# schematic_Nokia5110.net
KiCad netlist of a schematic drawn in EAGLE
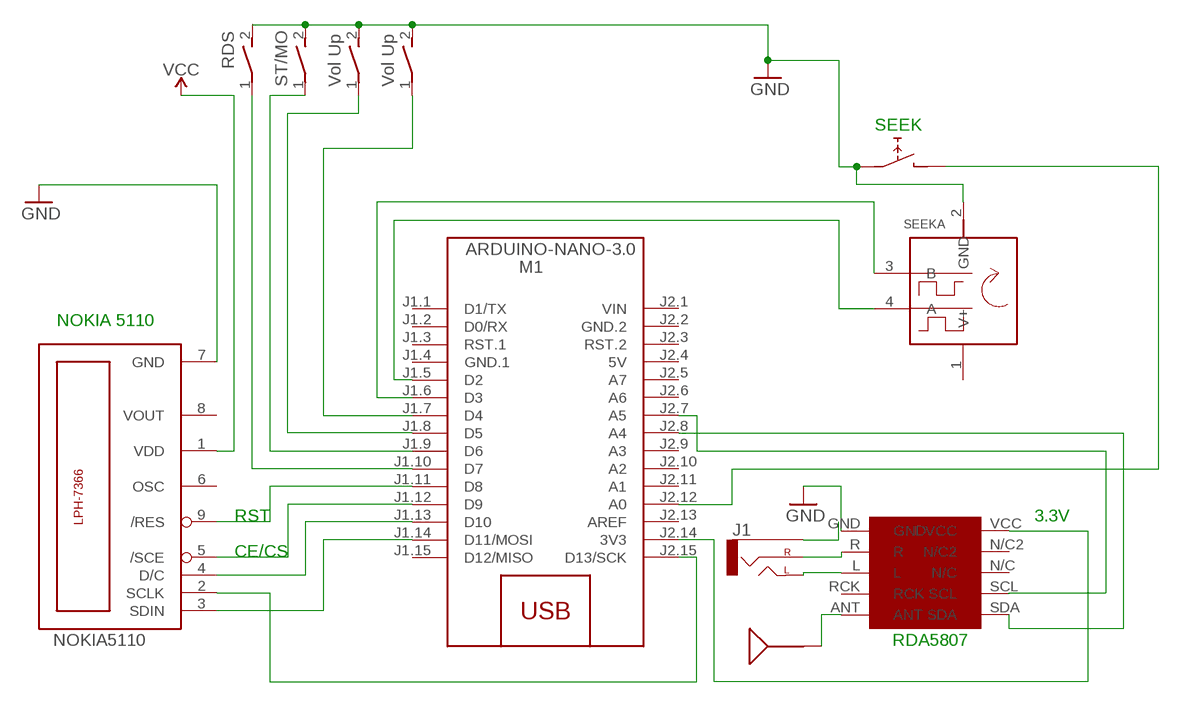
[diagram p0: schematic, sheet 1]

(export (version "E")
  (design (tool "Eeschema 10.0.6"))
  (components
    (comp (ref "A1")
      (value "ANTENNA-2.4GHZ-3.2X1.6MM")
      (footprint "eagle-import:ANT-2.4GHZ-3.2X1.6X1.2MM")
      (libsource (lib "eagle-import") (part "ANTENNA-2.4GHZ-3.2X1.6MM"))
    )
    (comp (ref "J1")
      (value "AUDIO_JACK_2.5MM_2.5MM")
      (footprint "eagle-import:STEREOJACK2.5MM_STEREOJACK2.5MM")
      (libsource (lib "eagle-import") (part "AUDIO_JACK_2.5MM_2.5MM"))
    )
    (comp (ref "M1")
      (value "ARDUINO-NANO-3.0")
      (footprint "eagle-import:ARDUINO-NANO-3.0")
      (libsource (lib "eagle-import") (part "ARDUINO-NANO-3.0"))
    )
    (comp (ref "NOKIA5110")
      (value "LPH-7366")
      (footprint "eagle-import:LPH-7366")
      (libsource (lib "eagle-import") (part "LPH-7366"))
    )
    (comp (ref "S1")
      (value "Vol Up")
      (footprint "eagle-import:DS-01")
      (libsource (lib "eagle-import") (part "DS01E"))
    )
    (comp (ref "S4")
      (value "Vol Up")
      (footprint "eagle-import:DS-01")
      (libsource (lib "eagle-import") (part "DS01E"))
    )
    (comp (ref "S5")
      (value "ST/MO")
      (footprint "eagle-import:DS-01")
      (libsource (lib "eagle-import") (part "DS01E"))
    )
    (comp (ref "S6")
      (value "RDS")
      (footprint "eagle-import:DS-01")
      (libsource (lib "eagle-import") (part "DS01E"))
    )
    (comp (ref "SEEK")
      (value "62P16-HX")
      (footprint "eagle-import:62P")
      (libsource (lib "eagle-import") (part "62PX16-H"))
    )
    (comp (ref "U$1")
      (value "RDA")
      (footprint "eagle-import:RDA")
      (libsource (lib "eagle-import") (part "RDA"))
    )
  )
  (nets
    (net (code "1") (name "/5V") (class "Default")
      (node (ref "M1") (pin "J2.4") (pinfunction "5V_J2.4") (pintype "power_in"))
    )
    (net (code "2") (name "/GND.1") (class "Default")
      (node (ref "M1") (pin "J1.4") (pinfunction "GND.1_J1.4") (pintype "power_in"))
    )
    (net (code "3") (name "/GND.2") (class "Default")
      (node (ref "M1") (pin "J2.2") (pinfunction "GND.2_J2.2") (pintype "power_in"))
    )
    (net (code "4") (name "/V+") (class "Default")
      (node (ref "SEEK") (pin "1") (pinfunction "V+_1") (pintype "power_in"))
    )
    (net (code "5") (name "/VIN") (class "Default")
      (node (ref "M1") (pin "J2.1") (pinfunction "VIN_J2.1") (pintype "power_in"))
    )
    (net (code "6") (name "GND") (class "Default")
      (node (ref "NOKIA5110") (pin "7") (pinfunction "GND_7") (pintype "power_in"))
      (node (ref "S1") (pin "2") (pinfunction "2_2") (pintype "passive"))
      (node (ref "S4") (pin "2") (pinfunction "2_2") (pintype "passive"))
      (node (ref "S5") (pin "2") (pinfunction "2_2") (pintype "passive"))
      (node (ref "S6") (pin "2") (pinfunction "2_2") (pintype "passive"))
      (node (ref "SEEK") (pin "2") (pinfunction "GND_2") (pintype "power_in"))
      (node (ref "SEEK") (pin "5") (pinfunction "D_5") (pintype "passive"))
      (node (ref "U$1") (pin "GND") (pinfunction "GND_GND") (pintype "power_in"))
    )
    (net (code "7") (name "Net-(A1-SIGNAL)") (class "Default")
      (node (ref "A1") (pin "FEED") (pinfunction "SIGNAL_FEED") (pintype "bidirectional"))
      (node (ref "U$1") (pin "ANT") (pinfunction "ANT_ANT") (pintype "input"))
    )
    (net (code "8") (name "Net-(J1-LEFT)") (class "Default")
      (node (ref "J1") (pin "SHIELD") (pinfunction "LEFT_SHIELD") (pintype "bidirectional"))
      (node (ref "U$1") (pin "L") (pinfunction "L_L") (pintype "output"))
    )
    (net (code "9") (name "Net-(J1-RIGHT)") (class "Default")
      (node (ref "J1") (pin "TIP") (pinfunction "RIGHT_TIP") (pintype "bidirectional"))
      (node (ref "U$1") (pin "R") (pinfunction "R_R") (pintype "output"))
    )
    (net (code "10") (name "Net-(M1-3V3)") (class "Default")
      (node (ref "M1") (pin "J2.14") (pinfunction "3V3_J2.14") (pintype "power_in"))
      (node (ref "U$1") (pin "VCC") (pinfunction "VCC_VCC") (pintype "power_in"))
    )
    (net (code "11") (name "Net-(M1-A0)") (class "Default")
      (node (ref "M1") (pin "J2.12") (pinfunction "A0_J2.12") (pintype "bidirectional"))
      (node (ref "SEEK") (pin "6") (pinfunction "E_6") (pintype "passive"))
    )
    (net (code "12") (name "Net-(M1-A4)") (class "Default")
      (node (ref "M1") (pin "J2.8") (pinfunction "A4_J2.8") (pintype "bidirectional"))
      (node (ref "U$1") (pin "SDA") (pinfunction "SDA_SDA") (pintype "bidirectional"))
    )
    (net (code "13") (name "Net-(M1-A5)") (class "Default")
      (node (ref "M1") (pin "J2.7") (pinfunction "A5_J2.7") (pintype "bidirectional"))
      (node (ref "U$1") (pin "SCL") (pinfunction "SCL_SCL") (pintype "bidirectional"))
    )
    (net (code "14") (name "Net-(M1-D2)") (class "Default")
      (node (ref "M1") (pin "J1.5") (pinfunction "D2_J1.5") (pintype "bidirectional"))
      (node (ref "SEEK") (pin "4") (pinfunction "A_4") (pintype "bidirectional"))
    )
    (net (code "15") (name "Net-(M1-D3)") (class "Default")
      (node (ref "M1") (pin "J1.6") (pinfunction "D3_J1.6") (pintype "bidirectional"))
      (node (ref "SEEK") (pin "3") (pinfunction "B_3") (pintype "bidirectional"))
    )
    (net (code "16") (name "Net-(M1-D4)") (class "Default")
      (node (ref "M1") (pin "J1.7") (pinfunction "D4_J1.7") (pintype "bidirectional"))
      (node (ref "S1") (pin "1") (pinfunction "1_1") (pintype "passive"))
    )
    (net (code "17") (name "Net-(M1-D5)") (class "Default")
      (node (ref "M1") (pin "J1.8") (pinfunction "D5_J1.8") (pintype "bidirectional"))
      (node (ref "S4") (pin "1") (pinfunction "1_1") (pintype "passive"))
    )
    (net (code "18") (name "Net-(M1-D6)") (class "Default")
      (node (ref "M1") (pin "J1.9") (pinfunction "D6_J1.9") (pintype "bidirectional"))
      (node (ref "S5") (pin "1") (pinfunction "1_1") (pintype "passive"))
    )
    (net (code "19") (name "Net-(M1-D7)") (class "Default")
      (node (ref "M1") (pin "J1.10") (pinfunction "D7_J1.10") (pintype "bidirectional"))
      (node (ref "S6") (pin "1") (pinfunction "1_1") (pintype "passive"))
    )
    (net (code "20") (name "Net-(M1-D8)") (class "Default")
      (node (ref "M1") (pin "J1.11") (pinfunction "D8_J1.11") (pintype "bidirectional"))
      (node (ref "NOKIA5110") (pin "9") (pinfunction "/RES_9") (pintype "input"))
    )
    (net (code "21") (name "Net-(M1-D9)") (class "Default")
      (node (ref "M1") (pin "J1.12") (pinfunction "D9_J1.12") (pintype "bidirectional"))
      (node (ref "NOKIA5110") (pin "5") (pinfunction "/SCE_5") (pintype "input"))
    )
    (net (code "22") (name "Net-(M1-D10)") (class "Default")
      (node (ref "M1") (pin "J1.13") (pinfunction "D10_J1.13") (pintype "bidirectional"))
      (node (ref "NOKIA5110") (pin "4") (pinfunction "D/C_4") (pintype "input"))
    )
    (net (code "23") (name "Net-(M1-D11{slash}MOSI)") (class "Default")
      (node (ref "M1") (pin "J1.14") (pinfunction "D11/MOSI_J1.14") (pintype "bidirectional"))
      (node (ref "NOKIA5110") (pin "3") (pinfunction "SDIN_3") (pintype "input"))
    )
    (net (code "24") (name "Net-(M1-D13{slash}SCK)") (class "Default")
      (node (ref "M1") (pin "J2.15") (pinfunction "D13/SCK_J2.15") (pintype "bidirectional"))
      (node (ref "NOKIA5110") (pin "2") (pinfunction "SCLK_2") (pintype "input"))
    )
    (net (code "25") (name "VCC") (class "Default")
      (node (ref "NOKIA5110") (pin "1") (pinfunction "VDD_1") (pintype "power_in"))
    )
    (net (code "26") (name "unconnected-(J1-SLEEVE-PadRING1)") (class "Default")
      (node (ref "J1") (pin "RING1") (pinfunction "SLEEVE_RING1") (pintype "bidirectional"))
    )
    (net (code "27") (name "unconnected-(M1-A1-PadJ2.11)") (class "Default")
      (node (ref "M1") (pin "J2.11") (pinfunction "A1_J2.11") (pintype "bidirectional"))
    )
    (net (code "28") (name "unconnected-(M1-A2-PadJ2.10)") (class "Default")
      (node (ref "M1") (pin "J2.10") (pinfunction "A2_J2.10") (pintype "bidirectional"))
    )
    (net (code "29") (name "unconnected-(M1-A3-PadJ2.9)") (class "Default")
      (node (ref "M1") (pin "J2.9") (pinfunction "A3_J2.9") (pintype "bidirectional"))
    )
    (net (code "30") (name "unconnected-(M1-A6-PadJ2.6)") (class "Default")
      (node (ref "M1") (pin "J2.6") (pinfunction "A6_J2.6") (pintype "bidirectional"))
    )
    (net (code "31") (name "unconnected-(M1-A7-PadJ2.5)") (class "Default")
      (node (ref "M1") (pin "J2.5") (pinfunction "A7_J2.5") (pintype "bidirectional"))
    )
    (net (code "32") (name "unconnected-(M1-AREF-PadJ2.13)") (class "Default")
      (node (ref "M1") (pin "J2.13") (pinfunction "AREF_J2.13") (pintype "bidirectional"))
    )
    (net (code "33") (name "unconnected-(M1-D0{slash}RX-PadJ1.2)") (class "Default")
      (node (ref "M1") (pin "J1.2") (pinfunction "D0/RX_J1.2") (pintype "bidirectional"))
    )
    (net (code "34") (name "unconnected-(M1-D1{slash}TX-PadJ1.1)") (class "Default")
      (node (ref "M1") (pin "J1.1") (pinfunction "D1/TX_J1.1") (pintype "bidirectional"))
    )
    (net (code "35") (name "unconnected-(M1-D12{slash}MISO-PadJ1.15)") (class "Default")
      (node (ref "M1") (pin "J1.15") (pinfunction "D12/MISO_J1.15") (pintype "bidirectional"))
    )
    (net (code "36") (name "unconnected-(M1-RST.1-PadJ1.3)") (class "Default")
      (node (ref "M1") (pin "J1.3") (pinfunction "RST.1_J1.3") (pintype "bidirectional"))
    )
    (net (code "37") (name "unconnected-(M1-RST.2-PadJ2.3)") (class "Default")
      (node (ref "M1") (pin "J2.3") (pinfunction "RST.2_J2.3") (pintype "bidirectional"))
    )
    (net (code "38") (name "unconnected-(NOKIA5110-OSC-Pad6)") (class "Default")
      (node (ref "NOKIA5110") (pin "6") (pinfunction "OSC_6") (pintype "passive"))
    )
    (net (code "39") (name "unconnected-(NOKIA5110-VOUT-Pad8)") (class "Default")
      (node (ref "NOKIA5110") (pin "8") (pinfunction "VOUT_8") (pintype "passive"))
    )
    (net (code "40") (name "unconnected-(U$1-PadN{slash}C)") (class "Default")
      (node (ref "U$1") (pin "N/C") (pinfunction "N/C_N/C") (pintype "passive"))
    )
    (net (code "41") (name "unconnected-(U$1-PadN{slash}C2)") (class "Default")
      (node (ref "U$1") (pin "N/C2") (pinfunction "N/C2_N/C2") (pintype "passive"))
    )
    (net (code "42") (name "unconnected-(U$1-PadRCK)") (class "Default")
      (node (ref "U$1") (pin "RCK") (pinfunction "RCK_RCK") (pintype "bidirectional"))
    )
  )
)
